# STMBreadboard.net
KiCad netlist of a schematic drawn in EAGLE
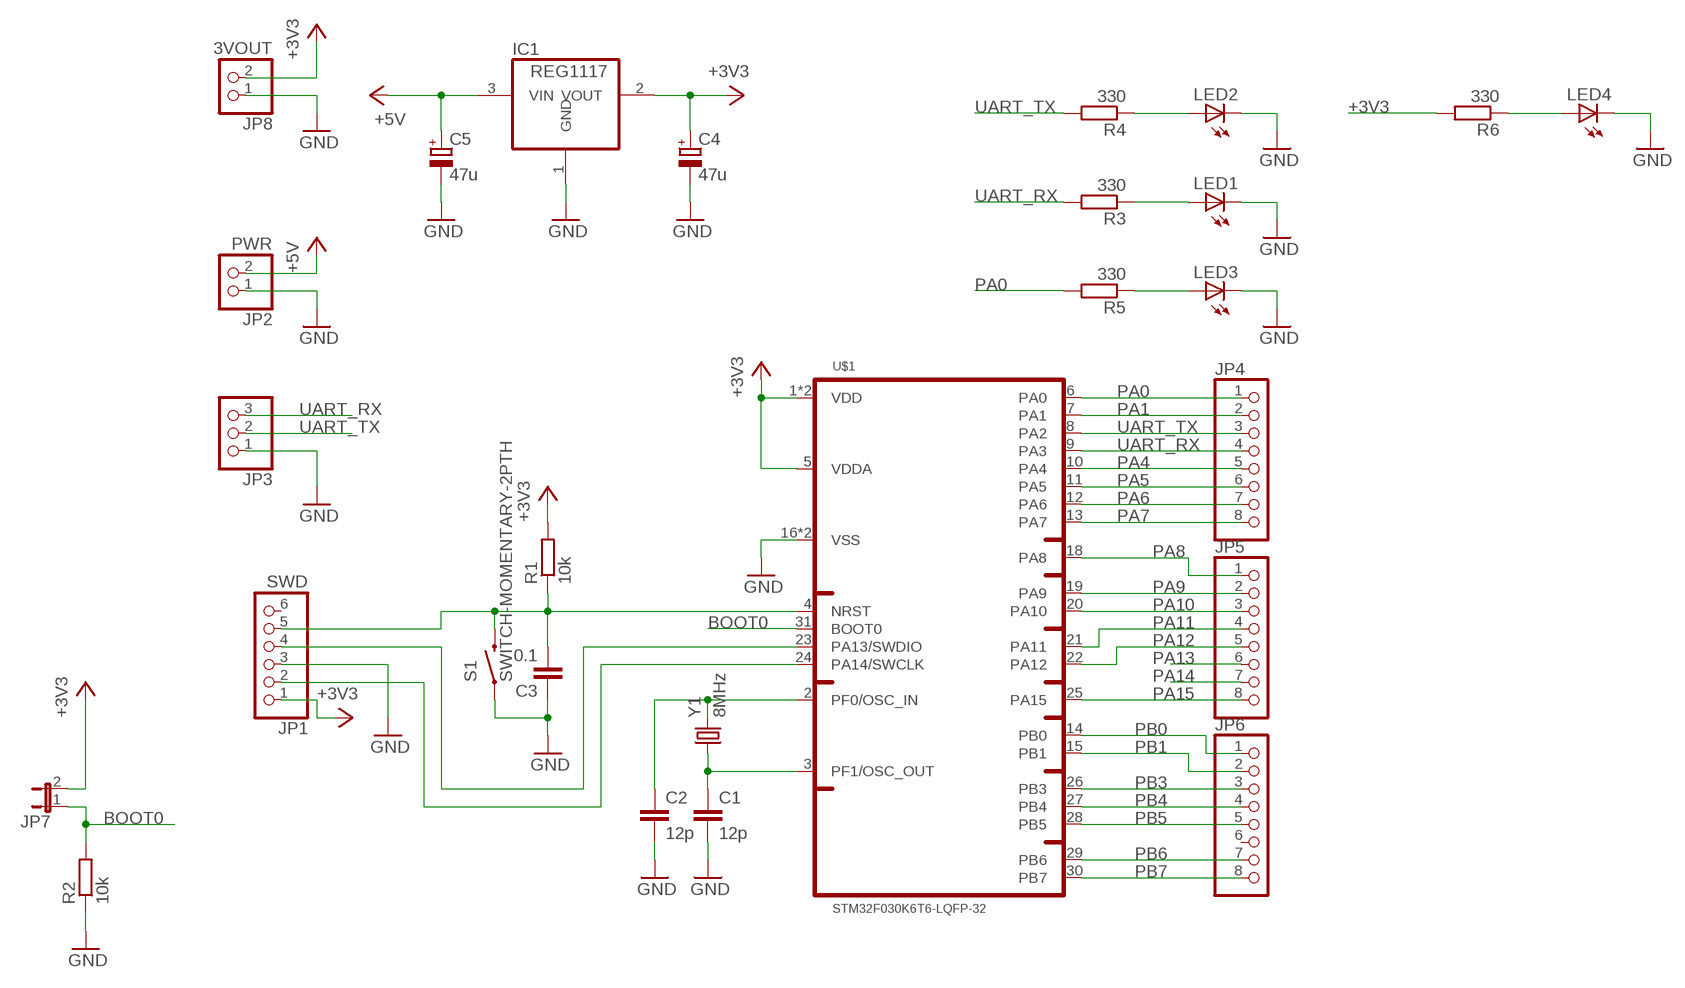
[diagram p0: schematic, sheet 1]

(export (version "E")
  (design (tool "Eeschema 10.0.6"))
  (components
    (comp (ref "C1")
      (value "12p")
      (footprint "eagle-import:C0805")
      (libsource (lib "eagle-import") (part "C-EUC0805"))
    )
    (comp (ref "C2")
      (value "12p")
      (footprint "eagle-import:C0805")
      (libsource (lib "eagle-import") (part "C-EUC0805"))
    )
    (comp (ref "C3")
      (value "0.1")
      (footprint "eagle-import:C0805")
      (libsource (lib "eagle-import") (part "C-EUC0805"))
    )
    (comp (ref "C4")
      (value "47u")
      (footprint "eagle-import:UD-6,3X7,7_NICHICON")
      (libsource (lib "eagle-import") (part "CPOL-EUUD-6,3X7,7"))
    )
    (comp (ref "C5")
      (value "47u")
      (footprint "eagle-import:UD-6,3X7,7_NICHICON")
      (libsource (lib "eagle-import") (part "CPOL-EUUD-6,3X7,7"))
    )
    (comp (ref "IC1")
      (value "REG1117")
      (footprint "eagle-import:SOT223")
      (libsource (lib "eagle-import") (part "REG1117"))
    )
    (comp (ref "JP1")
      (value "SWD")
      (footprint "eagle-import:1X06")
      (libsource (lib "eagle-import") (part "PINHD-1X6"))
    )
    (comp (ref "JP2")
      (value "PWR")
      (footprint "eagle-import:1X02")
      (libsource (lib "eagle-import") (part "PINHD-1X2"))
    )
    (comp (ref "JP3")
      (value "PINHD-1X3")
      (footprint "eagle-import:1X03")
      (libsource (lib "eagle-import") (part "PINHD-1X3"))
    )
    (comp (ref "JP4")
      (value "PINHD-1X8")
      (footprint "eagle-import:1X08")
      (libsource (lib "eagle-import") (part "PINHD-1X8"))
    )
    (comp (ref "JP5")
      (value "PINHD-1X8")
      (footprint "eagle-import:1X08")
      (libsource (lib "eagle-import") (part "PINHD-1X8"))
    )
    (comp (ref "JP6")
      (value "PINHD-1X8")
      (footprint "eagle-import:1X08")
      (libsource (lib "eagle-import") (part "PINHD-1X8"))
    )
    (comp (ref "JP7")
      (value "JP1E")
      (footprint "eagle-import:JP1")
      (libsource (lib "eagle-import") (part "JP1E"))
    )
    (comp (ref "JP8")
      (value "3VOUT")
      (footprint "eagle-import:1X02")
      (libsource (lib "eagle-import") (part "PINHD-1X2"))
    )
    (comp (ref "LED1")
      (value "LEDCHIPLED_0603")
      (footprint "eagle-import:CHIPLED_0603")
      (libsource (lib "eagle-import") (part "LEDCHIPLED_0603"))
    )
    (comp (ref "LED2")
      (value "LEDCHIPLED_0603")
      (footprint "eagle-import:CHIPLED_0603")
      (libsource (lib "eagle-import") (part "LEDCHIPLED_0603"))
    )
    (comp (ref "LED3")
      (value "LEDSML0603")
      (footprint "eagle-import:SML0603")
      (libsource (lib "eagle-import") (part "LEDSML0603"))
    )
    (comp (ref "LED4")
      (value "LEDSML0603")
      (footprint "eagle-import:SML0603")
      (libsource (lib "eagle-import") (part "LEDSML0603"))
    )
    (comp (ref "R1")
      (value "10k")
      (footprint "eagle-import:R1206")
      (libsource (lib "eagle-import") (part "R-EU_R1206"))
    )
    (comp (ref "R2")
      (value "10k")
      (footprint "eagle-import:R1206")
      (libsource (lib "eagle-import") (part "R-EU_R1206"))
    )
    (comp (ref "R3")
      (value "330")
      (footprint "eagle-import:R1206")
      (libsource (lib "eagle-import") (part "R-EU_R1206"))
    )
    (comp (ref "R4")
      (value "330")
      (footprint "eagle-import:R1206")
      (libsource (lib "eagle-import") (part "R-EU_R1206"))
    )
    (comp (ref "R5")
      (value "330")
      (footprint "eagle-import:R1206")
      (libsource (lib "eagle-import") (part "R-EU_R1206"))
    )
    (comp (ref "R6")
      (value "330")
      (footprint "eagle-import:R1206")
      (libsource (lib "eagle-import") (part "R-EU_R1206"))
    )
    (comp (ref "S1")
      (value "SWITCH-MOMENTARY-2PTH")
      (footprint "eagle-import:TACTILE-PTH")
      (libsource (lib "eagle-import") (part "SWITCH-MOMENTARY-2PTH"))
    )
    (comp (ref "U$1")
      (value "STM32F030K6T6-LQFP-32")
      (footprint "eagle-import:LQFP-32")
      (libsource (lib "eagle-import") (part "STM32F030K6T6-LQFP-32"))
    )
    (comp (ref "Y1")
      (value "8MHz")
      (footprint "eagle-import:HC49UP")
      (libsource (lib "eagle-import") (part "CRYSTALSMD"))
    )
  )
  (nets
    (net (code "1") (name "+3V3") (class "Default")
      (node (ref "C4") (pin "+") (pinfunction "+_+") (pintype "passive"))
      (node (ref "IC1") (pin "2") (pinfunction "VOUT_2") (pintype "output"))
      (node (ref "JP1") (pin "1") (pinfunction "1_1") (pintype "passive"))
      (node (ref "JP7") (pin "2") (pinfunction "2_2") (pintype "passive"))
      (node (ref "JP8") (pin "2") (pinfunction "2_2") (pintype "passive"))
      (node (ref "R1") (pin "2") (pinfunction "2_2") (pintype "passive"))
      (node (ref "R6") (pin "2") (pinfunction "2_2") (pintype "passive"))
      (node (ref "U$1") (pin "1") (pinfunction "VDD_1") (pintype "bidirectional"))
      (node (ref "U$1") (pin "17") (pinfunction "VDD_17") (pintype "bidirectional"))
      (node (ref "U$1") (pin "5") (pinfunction "VDDA_5") (pintype "bidirectional"))
    )
    (net (code "2") (name "+5V") (class "Default")
      (node (ref "C5") (pin "+") (pinfunction "+_+") (pintype "passive"))
      (node (ref "IC1") (pin "3") (pinfunction "VIN_3") (pintype "input"))
      (node (ref "JP2") (pin "2") (pinfunction "2_2") (pintype "passive"))
    )
    (net (code "3") (name "/BOOT0") (class "Default")
      (node (ref "JP7") (pin "1") (pinfunction "1_1") (pintype "passive"))
      (node (ref "R2") (pin "2") (pinfunction "2_2") (pintype "passive"))
      (node (ref "U$1") (pin "31") (pinfunction "BOOT0_31") (pintype "bidirectional"))
    )
    (net (code "4") (name "/PA0") (class "Default")
      (node (ref "JP4") (pin "1") (pinfunction "1_1") (pintype "passive"))
      (node (ref "R5") (pin "2") (pinfunction "2_2") (pintype "passive"))
      (node (ref "U$1") (pin "6") (pinfunction "PA0_6") (pintype "bidirectional"))
    )
    (net (code "5") (name "/PA1") (class "Default")
      (node (ref "JP4") (pin "2") (pinfunction "2_2") (pintype "passive"))
      (node (ref "U$1") (pin "7") (pinfunction "PA1_7") (pintype "bidirectional"))
    )
    (net (code "6") (name "/PA4") (class "Default")
      (node (ref "JP4") (pin "5") (pinfunction "5_5") (pintype "passive"))
      (node (ref "U$1") (pin "10") (pinfunction "PA4_10") (pintype "bidirectional"))
    )
    (net (code "7") (name "/PA5") (class "Default")
      (node (ref "JP4") (pin "6") (pinfunction "6_6") (pintype "passive"))
      (node (ref "U$1") (pin "11") (pinfunction "PA5_11") (pintype "bidirectional"))
    )
    (net (code "8") (name "/PA6") (class "Default")
      (node (ref "JP4") (pin "7") (pinfunction "7_7") (pintype "passive"))
      (node (ref "U$1") (pin "12") (pinfunction "PA6_12") (pintype "bidirectional"))
    )
    (net (code "9") (name "/PA7") (class "Default")
      (node (ref "JP4") (pin "8") (pinfunction "8_8") (pintype "passive"))
      (node (ref "U$1") (pin "13") (pinfunction "PA7_13") (pintype "bidirectional"))
    )
    (net (code "10") (name "/PA8") (class "Default")
      (node (ref "JP5") (pin "1") (pinfunction "1_1") (pintype "passive"))
      (node (ref "U$1") (pin "18") (pinfunction "PA8_18") (pintype "bidirectional"))
    )
    (net (code "11") (name "/PA9") (class "Default")
      (node (ref "JP5") (pin "2") (pinfunction "2_2") (pintype "passive"))
      (node (ref "U$1") (pin "19") (pinfunction "PA9_19") (pintype "bidirectional"))
    )
    (net (code "12") (name "/PA10") (class "Default")
      (node (ref "JP5") (pin "3") (pinfunction "3_3") (pintype "passive"))
      (node (ref "U$1") (pin "20") (pinfunction "PA10_20") (pintype "bidirectional"))
    )
    (net (code "13") (name "/PA11") (class "Default")
      (node (ref "JP5") (pin "4") (pinfunction "4_4") (pintype "passive"))
      (node (ref "U$1") (pin "21") (pinfunction "PA11_21") (pintype "bidirectional"))
    )
    (net (code "14") (name "/PA12") (class "Default")
      (node (ref "JP5") (pin "5") (pinfunction "5_5") (pintype "passive"))
      (node (ref "U$1") (pin "22") (pinfunction "PA12_22") (pintype "bidirectional"))
    )
    (net (code "15") (name "/PA13") (class "Default")
      (node (ref "JP1") (pin "4") (pinfunction "4_4") (pintype "passive"))
      (node (ref "JP5") (pin "6") (pinfunction "6_6") (pintype "passive"))
      (node (ref "U$1") (pin "23") (pinfunction "PA13/SWDIO_23") (pintype "bidirectional"))
    )
    (net (code "16") (name "/PA14") (class "Default")
      (node (ref "JP1") (pin "2") (pinfunction "2_2") (pintype "passive"))
      (node (ref "JP5") (pin "7") (pinfunction "7_7") (pintype "passive"))
      (node (ref "U$1") (pin "24") (pinfunction "PA14/SWCLK_24") (pintype "bidirectional"))
    )
    (net (code "17") (name "/PA15") (class "Default")
      (node (ref "JP5") (pin "8") (pinfunction "8_8") (pintype "passive"))
      (node (ref "U$1") (pin "25") (pinfunction "PA15_25") (pintype "bidirectional"))
    )
    (net (code "18") (name "/PB0") (class "Default")
      (node (ref "JP6") (pin "1") (pinfunction "1_1") (pintype "passive"))
      (node (ref "U$1") (pin "14") (pinfunction "PB0_14") (pintype "bidirectional"))
    )
    (net (code "19") (name "/PB1") (class "Default")
      (node (ref "JP6") (pin "2") (pinfunction "2_2") (pintype "passive"))
      (node (ref "U$1") (pin "15") (pinfunction "PB1_15") (pintype "bidirectional"))
    )
    (net (code "20") (name "/PB3") (class "Default")
      (node (ref "JP6") (pin "3") (pinfunction "3_3") (pintype "passive"))
      (node (ref "U$1") (pin "26") (pinfunction "PB3_26") (pintype "bidirectional"))
    )
    (net (code "21") (name "/PB4") (class "Default")
      (node (ref "JP6") (pin "4") (pinfunction "4_4") (pintype "passive"))
      (node (ref "U$1") (pin "27") (pinfunction "PB4_27") (pintype "bidirectional"))
    )
    (net (code "22") (name "/PB5") (class "Default")
      (node (ref "JP6") (pin "5") (pinfunction "5_5") (pintype "passive"))
      (node (ref "U$1") (pin "28") (pinfunction "PB5_28") (pintype "bidirectional"))
    )
    (net (code "23") (name "/PB6") (class "Default")
      (node (ref "JP6") (pin "7") (pinfunction "7_7") (pintype "passive"))
      (node (ref "U$1") (pin "29") (pinfunction "PB6_29") (pintype "bidirectional"))
    )
    (net (code "24") (name "/PB7") (class "Default")
      (node (ref "JP6") (pin "8") (pinfunction "8_8") (pintype "passive"))
      (node (ref "U$1") (pin "30") (pinfunction "PB7_30") (pintype "bidirectional"))
    )
    (net (code "25") (name "/UART_RX") (class "Default")
      (node (ref "JP3") (pin "3") (pinfunction "3_3") (pintype "passive"))
      (node (ref "JP4") (pin "4") (pinfunction "4_4") (pintype "passive"))
      (node (ref "R3") (pin "2") (pinfunction "2_2") (pintype "passive"))
      (node (ref "U$1") (pin "9") (pinfunction "PA3_9") (pintype "bidirectional"))
    )
    (net (code "26") (name "/UART_TX") (class "Default")
      (node (ref "JP3") (pin "2") (pinfunction "2_2") (pintype "passive"))
      (node (ref "JP4") (pin "3") (pinfunction "3_3") (pintype "passive"))
      (node (ref "R4") (pin "2") (pinfunction "2_2") (pintype "passive"))
      (node (ref "U$1") (pin "8") (pinfunction "PA2_8") (pintype "bidirectional"))
    )
    (net (code "27") (name "GND") (class "Default")
      (node (ref "C1") (pin "2") (pinfunction "2_2") (pintype "passive"))
      (node (ref "C2") (pin "2") (pinfunction "2_2") (pintype "passive"))
      (node (ref "C3") (pin "1") (pinfunction "1_1") (pintype "passive"))
      (node (ref "C4") (pin "-") (pinfunction "-_-") (pintype "passive"))
      (node (ref "C5") (pin "-") (pinfunction "-_-") (pintype "passive"))
      (node (ref "IC1") (pin "1") (pinfunction "GND_1") (pintype "power_in"))
      (node (ref "JP1") (pin "3") (pinfunction "3_3") (pintype "passive"))
      (node (ref "JP2") (pin "1") (pinfunction "1_1") (pintype "passive"))
      (node (ref "JP3") (pin "1") (pinfunction "1_1") (pintype "passive"))
      (node (ref "JP8") (pin "1") (pinfunction "1_1") (pintype "passive"))
      (node (ref "LED1") (pin "C") (pinfunction "C_C") (pintype "passive"))
      (node (ref "LED2") (pin "C") (pinfunction "C_C") (pintype "passive"))
      (node (ref "LED3") (pin "C") (pinfunction "C_C") (pintype "passive"))
      (node (ref "LED4") (pin "C") (pinfunction "C_C") (pintype "passive"))
      (node (ref "R2") (pin "1") (pinfunction "1_1") (pintype "passive"))
      (node (ref "S1") (pin "1") (pinfunction "1_1") (pintype "passive"))
      (node (ref "U$1") (pin "16") (pinfunction "VSS_16") (pintype "bidirectional"))
      (node (ref "U$1") (pin "32") (pinfunction "VSS_32") (pintype "bidirectional"))
    )
    (net (code "28") (name "Net-(LED1-PadA)") (class "Default")
      (node (ref "LED1") (pin "A") (pinfunction "A_A") (pintype "passive"))
      (node (ref "R3") (pin "1") (pinfunction "1_1") (pintype "passive"))
    )
    (net (code "29") (name "Net-(LED2-PadA)") (class "Default")
      (node (ref "LED2") (pin "A") (pinfunction "A_A") (pintype "passive"))
      (node (ref "R4") (pin "1") (pinfunction "1_1") (pintype "passive"))
    )
    (net (code "30") (name "Net-(LED3-PadA)") (class "Default")
      (node (ref "LED3") (pin "A") (pinfunction "A_A") (pintype "passive"))
      (node (ref "R5") (pin "1") (pinfunction "1_1") (pintype "passive"))
    )
    (net (code "31") (name "Net-(LED4-PadA)") (class "Default")
      (node (ref "LED4") (pin "A") (pinfunction "A_A") (pintype "passive"))
      (node (ref "R6") (pin "1") (pinfunction "1_1") (pintype "passive"))
    )
    (net (code "32") (name "Net-(S1-2)") (class "Default")
      (node (ref "C3") (pin "2") (pinfunction "2_2") (pintype "passive"))
      (node (ref "JP1") (pin "5") (pinfunction "5_5") (pintype "passive"))
      (node (ref "R1") (pin "1") (pinfunction "1_1") (pintype "passive"))
      (node (ref "S1") (pin "3") (pinfunction "2_3") (pintype "passive"))
      (node (ref "U$1") (pin "4") (pinfunction "NRST_4") (pintype "bidirectional"))
    )
    (net (code "33") (name "Net-(U$1-PF0{slash}OSC_IN)") (class "Default")
      (node (ref "C2") (pin "1") (pinfunction "1_1") (pintype "passive"))
      (node (ref "U$1") (pin "2") (pinfunction "PF0/OSC_IN_2") (pintype "bidirectional"))
      (node (ref "Y1") (pin "2") (pinfunction "2_2") (pintype "passive"))
    )
    (net (code "34") (name "Net-(U$1-PF1{slash}OSC_OUT)") (class "Default")
      (node (ref "C1") (pin "1") (pinfunction "1_1") (pintype "passive"))
      (node (ref "U$1") (pin "3") (pinfunction "PF1/OSC_OUT_3") (pintype "bidirectional"))
      (node (ref "Y1") (pin "1") (pinfunction "1_1") (pintype "passive"))
    )
    (net (code "35") (name "unconnected-(JP1-Pad6)") (class "Default")
      (node (ref "JP1") (pin "6") (pinfunction "6_6") (pintype "passive"))
    )
    (net (code "36") (name "unconnected-(JP6-Pad6)") (class "Default")
      (node (ref "JP6") (pin "6") (pinfunction "6_6") (pintype "passive"))
    )
  )
)
